# Si7006_Breakout_Board.net
KiCad netlist of a schematic drawn in EAGLE
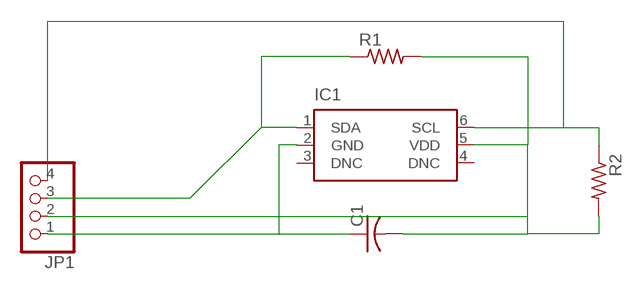
[diagram p0: schematic, sheet 1]

(export (version "E")
  (design (tool "Eeschema 10.0.6"))
  (components
    (comp (ref "C1")
      (value "C-USC0805")
      (footprint "eagle-import:C0805")
      (libsource (lib "eagle-import") (part "C-USC0805"))
    )
    (comp (ref "IC1")
      (value "SI7006-A10-IM")
      (footprint "eagle-import:DFN6-3X3")
      (fields (field (name "MF") "Silicon Labs") (field (name "MPN") "Si7006-A10-IM"))
      (libsource (lib "eagle-import") (part "SI7006-A10-IM"))
    )
    (comp (ref "JP1")
      (value "PINHD-1X4")
      (footprint "eagle-import:1X04")
      (libsource (lib "eagle-import") (part "PINHD-1X4"))
    )
    (comp (ref "R1")
      (value "R-US_R0805")
      (footprint "eagle-import:R0805")
      (libsource (lib "eagle-import") (part "R-US_R0805"))
    )
    (comp (ref "R2")
      (value "R-US_R0805")
      (footprint "eagle-import:R0805")
      (libsource (lib "eagle-import") (part "R-US_R0805"))
    )
  )
  (nets
    (net (code "1") (name "Net-(IC1-GND)") (class "Default")
      (node (ref "C1") (pin "1") (pinfunction "1_1") (pintype "passive"))
      (node (ref "IC1") (pin "2") (pinfunction "GND_2") (pintype "power_in"))
      (node (ref "JP1") (pin "1") (pinfunction "1_1") (pintype "passive"))
    )
    (net (code "2") (name "Net-(IC1-SCL)") (class "Default")
      (node (ref "IC1") (pin "6") (pinfunction "SCL_6") (pintype "input"))
      (node (ref "JP1") (pin "4") (pinfunction "4_4") (pintype "passive"))
      (node (ref "R2") (pin "1") (pinfunction "1_1") (pintype "passive"))
    )
    (net (code "3") (name "Net-(IC1-SDA)") (class "Default")
      (node (ref "IC1") (pin "1") (pinfunction "SDA_1") (pintype "bidirectional"))
      (node (ref "JP1") (pin "3") (pinfunction "3_3") (pintype "passive"))
      (node (ref "R1") (pin "1") (pinfunction "1_1") (pintype "passive"))
    )
    (net (code "4") (name "Net-(IC1-VDD)") (class "Default")
      (node (ref "C1") (pin "2") (pinfunction "2_2") (pintype "passive"))
      (node (ref "IC1") (pin "5") (pinfunction "VDD_5") (pintype "power_in"))
      (node (ref "JP1") (pin "2") (pinfunction "2_2") (pintype "passive"))
      (node (ref "R1") (pin "2") (pinfunction "2_2") (pintype "passive"))
      (node (ref "R2") (pin "2") (pinfunction "2_2") (pintype "passive"))
    )
    (net (code "5") (name "unconnected-(IC1-DNC-Pad3)") (class "Default")
      (node (ref "IC1") (pin "3") (pinfunction "DNC_3") (pintype "no_connect"))
    )
    (net (code "6") (name "unconnected-(IC1-DNC-Pad4)") (class "Default")
      (node (ref "IC1") (pin "4") (pinfunction "DNC_4") (pintype "no_connect"))
    )
  )
)
